# BikerBlinker.net
KiCad netlist of a schematic drawn in Altium Designer
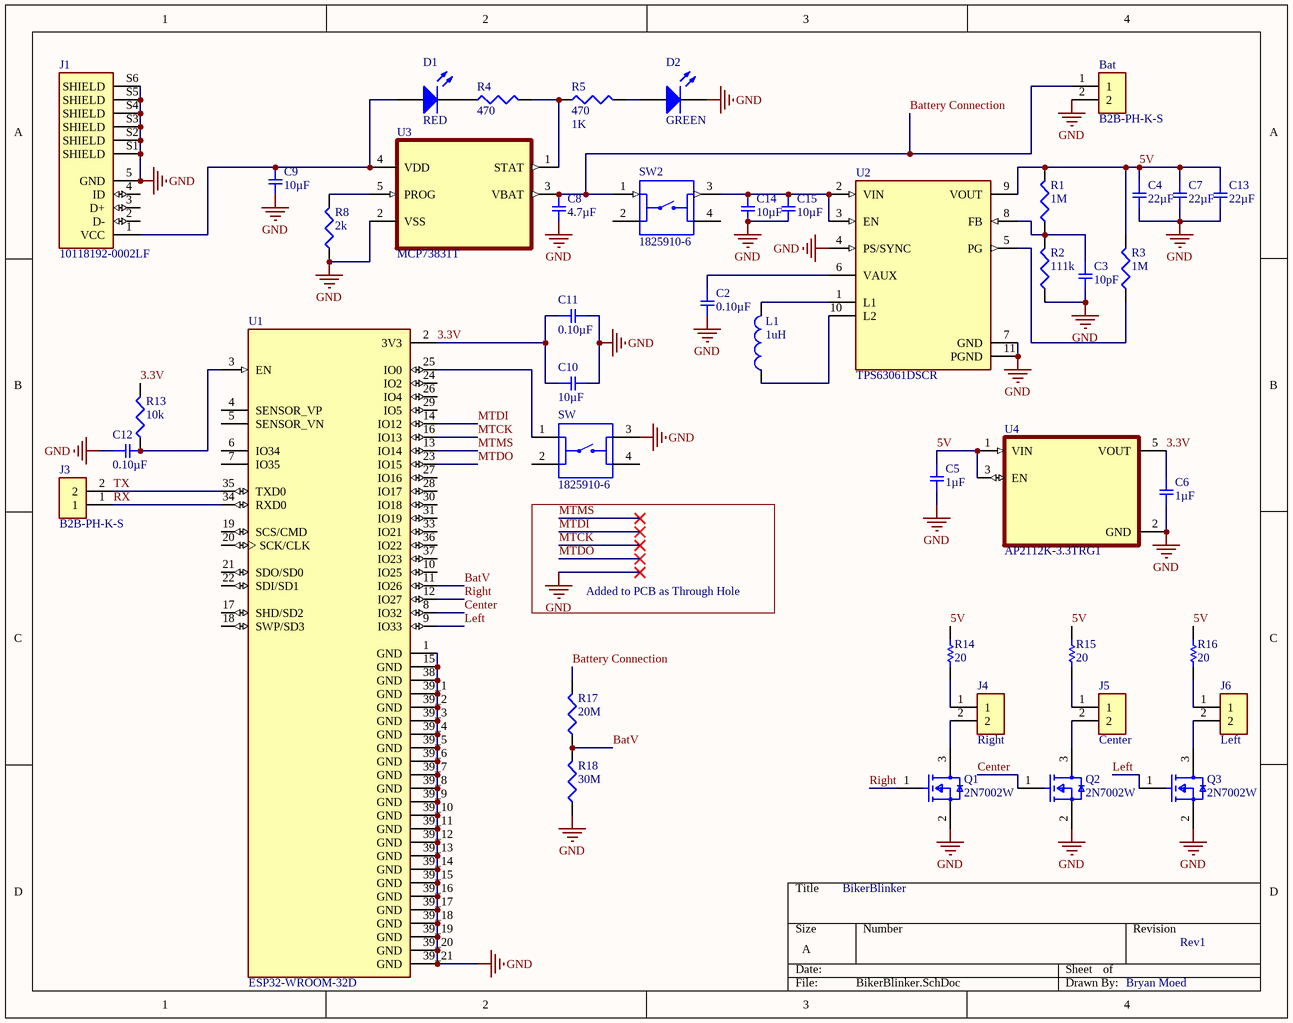
[diagram p0: BikerBlinker.SchDoc]

(export (version "E")
  (design (tool "Eeschema 10.0.6"))
  (components
    (comp (ref "Bat")
      (value "B2B-PH-K-S")
      (footprint "JST_B2B-PH-K-S(LF)(SN)")
      (description "Connector Header Through Hole 2 position 0.079 _2.00mm_")
      (fields (field (name "MF") "JST Sales") (field (name "MP") "B2B-PH-K-S_LF__SN_"))
      (libsource (lib "") (part "B2B-PH-K-S(LF)(SN)_1"))
    )
    (comp (ref "C2")
      (value "0.10µF")
      (footprint "SMD-0603C")
      (description "CAP CER 0.1UF 16V X7R 0603")
      (fields
        (field (name "DIGI-KEY PART NUMBER") "490-5796-1-ND")
        (field (name "PART NUMBER") "GCJ188R71C104KA01D")
      )
      (libsource (lib "capacitor_murata_0603") (part "GCJ188R71C104KA01D"))
    )
    (comp (ref "C3")
      (value "10pF")
      (footprint "SMD-0603C")
      (description "CAP CER 10PF 50V NP0 0603")
      (fields
        (field (name "DIGI-KEY PART NUMBER") "490-12530-1-ND")
        (field (name "PART NUMBER") "GCM1885C1H100FA16D")
      )
      (libsource (lib "capacitor_murata_0603") (part "GCM1885C1H100FA16D"))
    )
    (comp (ref "C4")
      (value "22µF")
      (footprint "SMD-0603C")
      (description "CAP CER 22UF 6.3V X5R 0603")
      (fields
        (field (name "DIGI-KEY PART NUMBER") "490-13241-1-ND")
        (field (name "PART NUMBER") "GRM186R60J226ME15D")
      )
      (libsource (lib "capacitor_murata_0603") (part "GRM186R60J226ME15D"))
    )
    (comp (ref "C5")
      (value "1µF")
      (footprint "SMD-0603C")
      (description "CAP CER 1UF 16V X7R 0603")
      (fields
        (field (name "DIGI-KEY PART NUMBER") "490-5241-1-ND")
        (field (name "PART NUMBER") "GCM188R71C105KA64D")
      )
      (libsource (lib "capacitor_murata_0603") (part "GCM188R71C105KA64D"))
    )
    (comp (ref "C6")
      (value "1µF")
      (footprint "SMD-0603C")
      (description "CAP CER 1UF 16V X7R 0603")
      (fields
        (field (name "DIGI-KEY PART NUMBER") "490-5241-1-ND")
        (field (name "PART NUMBER") "GCM188R71C105KA64D")
      )
      (libsource (lib "capacitor_murata_0603") (part "GCM188R71C105KA64D"))
    )
    (comp (ref "C7")
      (value "22µF")
      (footprint "SMD-0603C")
      (description "CAP CER 22UF 6.3V X5R 0603")
      (fields
        (field (name "DIGI-KEY PART NUMBER") "490-13241-1-ND")
        (field (name "PART NUMBER") "GRM186R60J226ME15D")
      )
      (libsource (lib "capacitor_murata_0603") (part "GRM186R60J226ME15D"))
    )
    (comp (ref "C8")
      (value "4.7µF")
      (footprint "SMD-0603C")
      (description "CAP CER 4.7UF 6.3V X7S 0603")
      (fields
        (field (name "DIGI-KEY PART NUMBER") "490-10884-1-ND")
        (field (name "PART NUMBER") "GRJ188C70J475KE11D")
      )
      (libsource (lib "capacitor_murata_0603") (part "GRJ188C70J475KE11D"))
    )
    (comp (ref "C9")
      (value "10µF")
      (footprint "SMD-0603C")
      (description "CAP CER 10UF 6.3V X5R 0603")
      (fields
        (field (name "DIGI-KEY PART NUMBER") "490-10467-1-ND")
        (field (name "PART NUMBER") "GRM185R60J106ME15D")
      )
      (libsource (lib "capacitor_murata_0603") (part "GRM185R60J106ME15D"))
    )
    (comp (ref "C10")
      (value "10µF")
      (footprint "SMD-0603C")
      (description "CAP CER 10UF 6.3V X5R 0603")
      (fields
        (field (name "DIGI-KEY PART NUMBER") "490-10467-1-ND")
        (field (name "PART NUMBER") "GRM185R60J106ME15D")
      )
      (libsource (lib "capacitor_murata_0603") (part "GRM185R60J106ME15D"))
    )
    (comp (ref "C11")
      (value "0.10µF")
      (footprint "SMD-0603C")
      (description "CAP CER 0.1UF 16V X7R 0603")
      (fields
        (field (name "DIGI-KEY PART NUMBER") "490-5796-1-ND")
        (field (name "PART NUMBER") "GCJ188R71C104KA01D")
      )
      (libsource (lib "capacitor_murata_0603") (part "GCJ188R71C104KA01D"))
    )
    (comp (ref "C12")
      (value "0.10µF")
      (footprint "SMD-0603C")
      (description "CAP CER 0.1UF 16V X7R 0603")
      (fields
        (field (name "DIGI-KEY PART NUMBER") "490-5796-1-ND")
        (field (name "PART NUMBER") "GCJ188R71C104KA01D")
      )
      (libsource (lib "capacitor_murata_0603") (part "GCJ188R71C104KA01D"))
    )
    (comp (ref "C13")
      (value "22µF")
      (footprint "SMD-0603C")
      (description "CAP CER 22UF 6.3V X5R 0603")
      (fields
        (field (name "DIGI-KEY PART NUMBER") "490-13241-1-ND")
        (field (name "PART NUMBER") "GRM186R60J226ME15D")
      )
      (libsource (lib "capacitor_murata_0603") (part "GRM186R60J226ME15D"))
    )
    (comp (ref "C14")
      (value "10µF")
      (footprint "SMD-0603C")
      (description "CAP CER 10UF 6.3V X5R 0603")
      (fields
        (field (name "DIGI-KEY PART NUMBER") "490-10467-1-ND")
        (field (name "PART NUMBER") "GRM185R60J106ME15D")
      )
      (libsource (lib "capacitor_murata_0603") (part "GRM185R60J106ME15D"))
    )
    (comp (ref "C15")
      (value "10µF")
      (footprint "SMD-0603C")
      (description "CAP CER 10UF 6.3V X5R 0603")
      (fields
        (field (name "DIGI-KEY PART NUMBER") "490-10467-1-ND")
        (field (name "PART NUMBER") "GRM185R60J106ME15D")
      )
      (libsource (lib "capacitor_murata_0603") (part "GRM185R60J106ME15D"))
    )
    (comp (ref "D1")
      (value "RED")
      (footprint "J1-0603")
      (description "Typical RED GaAs LED")
      (fields (field (name "PUBLISHER") "Altium Limited"))
      (libsource (lib "Miscellaneous Devices") (part "LED1"))
    )
    (comp (ref "D2")
      (value "GREEN")
      (footprint "J1-0603")
      (description "Typical RED GaAs LED")
      (fields (field (name "PUBLISHER") "Altium Limited"))
      (libsource (lib "Miscellaneous Devices") (part "LED1"))
    )
    (comp (ref "J1")
      (value "10118192-0002LF")
      (footprint "AMPHENOL_10118192-0002LF")
      (description "USB - micro B USB 2.0 Receptacle Connector 5 Position Surface Mount, Right Angle")
      (fields (field (name "MF") "Amphenol ICC"))
      (libsource (lib "10118192-0002LF") (part "10118192-0002LF"))
    )
    (comp (ref "J3")
      (value "B2B-PH-K-S")
      (footprint "JST_B2B-PH-K-S(LF)(SN)")
      (description "Connector Header Through Hole 2 position 0.079 _2.00mm_")
      (fields (field (name "MF") "JST Sales") (field (name "MP") "B2B-PH-K-S_LF__SN_"))
      (libsource (lib "B2B-PH-K-S_LF__SN_") (part "B2B-PH-K-S(LF)(SN)"))
    )
    (comp (ref "J4")
      (value "Right")
      (footprint "JST_B2B-PH-K-S(LF)(SN)")
      (description "Connector Header Through Hole 2 position 0.079 _2.00mm_")
      (fields (field (name "MF") "JST Sales") (field (name "MP") "B2B-PH-K-S_LF__SN_"))
      (libsource (lib "") (part "B2B-PH-K-S(LF)(SN)_1"))
    )
    (comp (ref "J5")
      (value "Center")
      (footprint "JST_B2B-PH-K-S(LF)(SN)")
      (description "Connector Header Through Hole 2 position 0.079 _2.00mm_")
      (fields (field (name "MF") "JST Sales") (field (name "MP") "B2B-PH-K-S_LF__SN_"))
      (libsource (lib "") (part "B2B-PH-K-S(LF)(SN)_1"))
    )
    (comp (ref "J6")
      (value "Left")
      (footprint "JST_B2B-PH-K-S(LF)(SN)")
      (description "Connector Header Through Hole 2 position 0.079 _2.00mm_")
      (fields (field (name "MF") "JST Sales") (field (name "MP") "B2B-PH-K-S_LF__SN_"))
      (libsource (lib "") (part "B2B-PH-K-S(LF)(SN)_1"))
    )
    (comp (ref "L1")
      (value "1uH")
      (footprint "0603")
      (description "Inductor")
      (fields (field (name "PUBLISHER") "Altium Limited"))
      (libsource (lib "Miscellaneous Devices") (part "Inductor"))
    )
    (comp (ref "Q1")
      (value "2N7002W")
      (footprint "FP-419AB-01-IPC_C")
      (description "MOSFET N-CH 60V 115MA SOT-323")
      (libsource (lib "Altium Content Vault") (part "a04dfd38ebfed9f67ad7f4c51a87371"))
    )
    (comp (ref "Q2")
      (value "2N7002W")
      (footprint "FP-419AB-01-IPC_C")
      (description "MOSFET N-CH 60V 115MA SOT-323")
      (libsource (lib "Altium Content Vault") (part "a04dfd38ebfed9f67ad7f4c51a87371"))
    )
    (comp (ref "Q3")
      (value "2N7002W")
      (footprint "FP-419AB-01-IPC_C")
      (description "MOSFET N-CH 60V 115MA SOT-323")
      (libsource (lib "Altium Content Vault") (part "a04dfd38ebfed9f67ad7f4c51a87371"))
    )
    (comp (ref "R1")
      (value "1M")
      (footprint "J1-0603")
      (description "Resistor")
      (fields (field (name "PUBLISHER") "Altium Limited"))
      (libsource (lib "Miscellaneous Devices") (part "Res3"))
    )
    (comp (ref "R2")
      (value "111k")
      (footprint "J1-0603")
      (description "Resistor")
      (fields (field (name "PUBLISHER") "Altium Limited"))
      (libsource (lib "Miscellaneous Devices") (part "Res3"))
    )
    (comp (ref "R3")
      (value "1M")
      (footprint "J1-0603")
      (description "Resistor")
      (fields (field (name "PUBLISHER") "Altium Limited"))
      (libsource (lib "Miscellaneous Devices") (part "Res3"))
    )
    (comp (ref "R4")
      (value "470")
      (footprint "J1-0603")
      (description "Resistor")
      (fields (field (name "PUBLISHER") "Altium Limited"))
      (libsource (lib "Miscellaneous Devices") (part "Res3"))
    )
    (comp (ref "R5")
      (value "470")
      (footprint "J1-0603")
      (description "Resistor")
      (fields (field (name "ALTIUM_VALUE") "1K") (field (name "PUBLISHER") "Altium Limited"))
      (libsource (lib "Miscellaneous Devices") (part "Res3"))
    )
    (comp (ref "R8")
      (value "2k")
      (footprint "J1-0603")
      (description "Resistor")
      (fields (field (name "PUBLISHER") "Altium Limited"))
      (libsource (lib "Miscellaneous Devices") (part "Res3"))
    )
    (comp (ref "R13")
      (value "10k")
      (footprint "J1-0603")
      (description "Resistor")
      (fields (field (name "PUBLISHER") "Altium Limited"))
      (libsource (lib "Miscellaneous Devices") (part "Res3"))
    )
    (comp (ref "R14")
      (value "20")
      (footprint "AXIAL-0.3")
      (description "Resistor")
      (fields (field (name "PUBLISHER") "Altium Limited"))
      (libsource (lib "Miscellaneous Devices") (part "Res1"))
    )
    (comp (ref "R15")
      (value "20")
      (footprint "AXIAL-0.3")
      (description "Resistor")
      (fields (field (name "PUBLISHER") "Altium Limited"))
      (libsource (lib "Miscellaneous Devices") (part "Res1"))
    )
    (comp (ref "R16")
      (value "20")
      (footprint "AXIAL-0.3")
      (description "Resistor")
      (fields (field (name "PUBLISHER") "Altium Limited"))
      (libsource (lib "Miscellaneous Devices") (part "Res1"))
    )
    (comp (ref "R17")
      (value "20M")
      (footprint "J1-0603")
      (description "Resistor")
      (fields (field (name "PUBLISHER") "Altium Limited"))
      (libsource (lib "Miscellaneous Devices") (part "Res3"))
    )
    (comp (ref "R18")
      (value "30M")
      (footprint "J1-0603")
      (description "Resistor")
      (fields (field (name "PUBLISHER") "Altium Limited"))
      (libsource (lib "Miscellaneous Devices") (part "Res3"))
    )
    (comp (ref "SW")
      (value "1825910-6")
      (footprint "SW_1825910-6-4")
      (description "Switch Push Button OFF _ON_ SPST Round Button 0.05A 24VDC Momentary Contact PC Pins Thru-Hole")
      (fields (field (name "MF") "TE Connectivity") (field (name "DIGI-KEY_PART_NUMBER") "450-1650-ND"))
      (libsource (lib "1825910-6") (part "1825910-6"))
    )
    (comp (ref "SW2")
      (value "1825910-6")
      (footprint "SW_1825910-6-4")
      (description "Switch Push Button OFF _ON_ SPST Round Button 0.05A 24VDC Momentary Contact PC Pins Thru-Hole")
      (fields (field (name "MF") "TE Connectivity") (field (name "DIGI-KEY_PART_NUMBER") "450-1650-ND"))
      (libsource (lib "1825910-6") (part "1825910-6"))
    )
    (comp (ref "U1")
      (value "ESP32-WROOM-32D")
      (footprint "MODULE_ESP32-WROOM-32D")
      (fields (field (name "MF") "Espressif Systems"))
      (libsource (lib "ESP32-WROOM-32D") (part "ESP32-WROOM-32D"))
    )
    (comp (ref "U2")
      (value "TPS63061DSCR")
      (footprint "CONV_TPS63061DSCR")
      (libsource (lib "TPS63061DSCR") (part "TPS63061DSCR"))
    )
    (comp (ref "U3")
      (value "MCP73831T")
      (footprint "SOT95P280X145-5N")
      (description "Charger IC Lithium Ion/Polymer SOT-23-5")
      (fields (field (name "MP") "MCP73831T-4ADI/OT") (field (name "MF") "Microchip"))
      (libsource (lib "MCP73831T-4ADI_OT") (part "MCP73831T-4ADI/OT"))
    )
    (comp (ref "U4")
      (value "AP2112K-3.3TRG1")
      (footprint "SOT95P285X140-5N")
      (description "Linear Voltage Regulator IC 1 Output 600mA SOT-25")
      (fields (field (name "MF") "Diodes Inc."))
      (libsource (lib "AP2112K-1.8TRG1") (part "AP2112K-1.8TRG1"))
    )
  )
  (nets
    (net (code "1") (name "/3.3V") (class "Default")
      (node (ref "C10") (pin "1") (pinfunction "1_1") (pintype "passive"))
      (node (ref "C11") (pin "1") (pinfunction "1_1") (pintype "passive"))
      (node (ref "C6") (pin "1") (pinfunction "1_1") (pintype "passive"))
      (node (ref "R13") (pin "2") (pinfunction "2_2") (pintype "passive"))
      (node (ref "U1") (pin "2") (pinfunction "3V3_2") (pintype "power_in"))
      (node (ref "U4") (pin "5") (pinfunction "VOUT_5") (pintype "power_in"))
    )
    (net (code "2") (name "/5V") (class "Default")
      (node (ref "C13") (pin "1") (pinfunction "1_1") (pintype "passive"))
      (node (ref "C4") (pin "1") (pinfunction "1_1") (pintype "passive"))
      (node (ref "C5") (pin "1") (pinfunction "1_1") (pintype "passive"))
      (node (ref "C7") (pin "1") (pinfunction "1_1") (pintype "passive"))
      (node (ref "R1") (pin "2") (pinfunction "2_2") (pintype "passive"))
      (node (ref "R14") (pin "2") (pinfunction "2_2") (pintype "passive"))
      (node (ref "R15") (pin "2") (pinfunction "2_2") (pintype "passive"))
      (node (ref "R16") (pin "2") (pinfunction "2_2") (pintype "passive"))
      (node (ref "R3") (pin "2") (pinfunction "2_2") (pintype "passive"))
      (node (ref "U2") (pin "9") (pinfunction "VOUT_9") (pintype "power_in"))
      (node (ref "U4") (pin "1") (pinfunction "VIN_1") (pintype "input"))
      (node (ref "U4") (pin "3") (pinfunction "EN_3") (pintype "bidirectional"))
    )
    (net (code "3") (name "/BatV") (class "Default")
      (node (ref "R17") (pin "1") (pinfunction "1_1") (pintype "passive"))
      (node (ref "R18") (pin "2") (pinfunction "2_2") (pintype "passive"))
      (node (ref "U1") (pin "11") (pinfunction "IO26_11") (pintype "bidirectional"))
    )
    (net (code "4") (name "/Battery Connection") (class "Default")
      (node (ref "Bat") (pin "1") (pinfunction "1_1") (pintype "passive"))
      (node (ref "C8") (pin "1") (pinfunction "1_1") (pintype "passive"))
      (node (ref "R17") (pin "2") (pinfunction "2_2") (pintype "passive"))
      (node (ref "SW2") (pin "1") (pinfunction "1_1") (pintype "passive"))
      (node (ref "U3") (pin "3") (pinfunction "VBAT_3") (pintype "output"))
    )
    (net (code "5") (name "/Center") (class "Default")
      (node (ref "Q2") (pin "1") (pinfunction "Gate_1") (pintype "passive"))
      (node (ref "U1") (pin "8") (pinfunction "IO32_8") (pintype "bidirectional"))
    )
    (net (code "6") (name "/Left") (class "Default")
      (node (ref "Q3") (pin "1") (pinfunction "Gate_1") (pintype "passive"))
      (node (ref "U1") (pin "9") (pinfunction "IO33_9") (pintype "bidirectional"))
    )
    (net (code "7") (name "/MTCK") (class "Default")
      (node (ref "U1") (pin "16") (pinfunction "IO13_16") (pintype "bidirectional"))
    )
    (net (code "8") (name "/MTDI") (class "Default")
      (node (ref "U1") (pin "14") (pinfunction "IO12_14") (pintype "bidirectional"))
    )
    (net (code "9") (name "/MTDO") (class "Default")
      (node (ref "U1") (pin "23") (pinfunction "IO15_23") (pintype "bidirectional"))
    )
    (net (code "10") (name "/MTMS") (class "Default")
      (node (ref "U1") (pin "13") (pinfunction "IO14_13") (pintype "bidirectional"))
    )
    (net (code "11") (name "/RX") (class "Default")
      (node (ref "J3") (pin "1") (pinfunction "1_1") (pintype "passive"))
      (node (ref "U1") (pin "34") (pinfunction "RXD0_34") (pintype "bidirectional"))
    )
    (net (code "12") (name "/Right") (class "Default")
      (node (ref "Q1") (pin "1") (pinfunction "Gate_1") (pintype "passive"))
      (node (ref "U1") (pin "12") (pinfunction "IO27_12") (pintype "bidirectional"))
    )
    (net (code "13") (name "/TX") (class "Default")
      (node (ref "J3") (pin "2") (pinfunction "2_2") (pintype "passive"))
      (node (ref "U1") (pin "35") (pinfunction "TXD0_35") (pintype "bidirectional"))
    )
    (net (code "14") (name "GND") (class "Default")
      (node (ref "Bat") (pin "2") (pinfunction "2_2") (pintype "passive"))
      (node (ref "C10") (pin "2") (pinfunction "2_2") (pintype "passive"))
      (node (ref "C11") (pin "2") (pinfunction "2_2") (pintype "passive"))
      (node (ref "C12") (pin "1") (pinfunction "1_1") (pintype "passive"))
      (node (ref "C13") (pin "2") (pinfunction "2_2") (pintype "passive"))
      (node (ref "C14") (pin "2") (pinfunction "2_2") (pintype "passive"))
      (node (ref "C15") (pin "2") (pinfunction "2_2") (pintype "passive"))
      (node (ref "C2") (pin "2") (pinfunction "2_2") (pintype "passive"))
      (node (ref "C3") (pin "2") (pinfunction "2_2") (pintype "passive"))
      (node (ref "C4") (pin "2") (pinfunction "2_2") (pintype "passive"))
      (node (ref "C5") (pin "2") (pinfunction "2_2") (pintype "passive"))
      (node (ref "C6") (pin "2") (pinfunction "2_2") (pintype "passive"))
      (node (ref "C7") (pin "2") (pinfunction "2_2") (pintype "passive"))
      (node (ref "C8") (pin "2") (pinfunction "2_2") (pintype "passive"))
      (node (ref "C9") (pin "2") (pinfunction "2_2") (pintype "passive"))
      (node (ref "D2") (pin "2") (pinfunction "K_2") (pintype "passive"))
      (node (ref "J1") (pin "5") (pinfunction "GND_5") (pintype "power_in"))
      (node (ref "J1") (pin "S1") (pinfunction "SHIELD_S1") (pintype "passive"))
      (node (ref "J1") (pin "S2") (pinfunction "SHIELD_S2") (pintype "passive"))
      (node (ref "J1") (pin "S3") (pinfunction "SHIELD_S3") (pintype "passive"))
      (node (ref "J1") (pin "S4") (pinfunction "SHIELD_S4") (pintype "passive"))
      (node (ref "J1") (pin "S5") (pinfunction "SHIELD_S5") (pintype "passive"))
      (node (ref "J1") (pin "S6") (pinfunction "SHIELD_S6") (pintype "passive"))
      (node (ref "Q1") (pin "2") (pinfunction "Source_2") (pintype "passive"))
      (node (ref "Q2") (pin "2") (pinfunction "Source_2") (pintype "passive"))
      (node (ref "Q3") (pin "2") (pinfunction "Source_2") (pintype "passive"))
      (node (ref "R18") (pin "1") (pinfunction "1_1") (pintype "passive"))
      (node (ref "R2") (pin "1") (pinfunction "1_1") (pintype "passive"))
      (node (ref "R8") (pin "1") (pinfunction "1_1") (pintype "passive"))
      (node (ref "SW") (pin "3") (pinfunction "3_3") (pintype "passive"))
      (node (ref "U1") (pin "1") (pinfunction "GND_1") (pintype "power_in"))
      (node (ref "U1") (pin "15") (pinfunction "GND_15") (pintype "power_in"))
      (node (ref "U1") (pin "38") (pinfunction "GND_38") (pintype "power_in"))
      (node (ref "U1") (pin "39_1") (pinfunction "GND_39_1") (pintype "power_in"))
      (node (ref "U1") (pin "39_10") (pinfunction "GND_39_10") (pintype "power_in"))
      (node (ref "U1") (pin "39_11") (pinfunction "GND_39_11") (pintype "power_in"))
      (node (ref "U1") (pin "39_12") (pinfunction "GND_39_12") (pintype "power_in"))
      (node (ref "U1") (pin "39_13") (pinfunction "GND_39_13") (pintype "power_in"))
      (node (ref "U1") (pin "39_14") (pinfunction "GND_39_14") (pintype "power_in"))
      (node (ref "U1") (pin "39_15") (pinfunction "GND_39_15") (pintype "power_in"))
      (node (ref "U1") (pin "39_16") (pinfunction "GND_39_16") (pintype "power_in"))
      (node (ref "U1") (pin "39_17") (pinfunction "GND_39_17") (pintype "power_in"))
      (node (ref "U1") (pin "39_18") (pinfunction "GND_39_18") (pintype "power_in"))
      (node (ref "U1") (pin "39_19") (pinfunction "GND_39_19") (pintype "power_in"))
      (node (ref "U1") (pin "39_2") (pinfunction "GND_39_2") (pintype "power_in"))
      (node (ref "U1") (pin "39_20") (pinfunction "GND_39_20") (pintype "power_in"))
      (node (ref "U1") (pin "39_21") (pinfunction "GND_39_21") (pintype "power_in"))
      (node (ref "U1") (pin "39_3") (pinfunction "GND_39_3") (pintype "power_in"))
      (node (ref "U1") (pin "39_4") (pinfunction "GND_39_4") (pintype "power_in"))
      (node (ref "U1") (pin "39_5") (pinfunction "GND_39_5") (pintype "power_in"))
      (node (ref "U1") (pin "39_6") (pinfunction "GND_39_6") (pintype "power_in"))
      (node (ref "U1") (pin "39_7") (pinfunction "GND_39_7") (pintype "power_in"))
      (node (ref "U1") (pin "39_8") (pinfunction "GND_39_8") (pintype "power_in"))
      (node (ref "U1") (pin "39_9") (pinfunction "GND_39_9") (pintype "power_in"))
      (node (ref "U2") (pin "11") (pinfunction "PGND_11") (pintype "power_in"))
      (node (ref "U2") (pin "4") (pinfunction "PS/SYNC_4") (pintype "input"))
      (node (ref "U2") (pin "7") (pinfunction "GND_7") (pintype "power_in"))
      (node (ref "U3") (pin "2") (pinfunction "VSS_2") (pintype "power_in"))
      (node (ref "U4") (pin "2") (pinfunction "GND_2") (pintype "power_in"))
    )
    (net (code "15") (name "Net-(D1-A)") (class "Default")
      (node (ref "C9") (pin "1") (pinfunction "1_1") (pintype "passive"))
      (node (ref "D1") (pin "1") (pinfunction "A_1") (pintype "passive"))
      (node (ref "J1") (pin "1") (pinfunction "VCC_1") (pintype "power_in"))
      (node (ref "U3") (pin "4") (pinfunction "VDD_4") (pintype "power_in"))
    )
    (net (code "16") (name "Net-(D1-K)") (class "Default")
      (node (ref "D1") (pin "2") (pinfunction "K_2") (pintype "passive"))
      (node (ref "R4") (pin "1") (pinfunction "1_1") (pintype "passive"))
    )
    (net (code "17") (name "Net-(D2-A)") (class "Default")
      (node (ref "D2") (pin "1") (pinfunction "A_1") (pintype "passive"))
      (node (ref "R5") (pin "2") (pinfunction "2_2") (pintype "passive"))
    )
    (net (code "18") (name "Net-(J4-Pad1)") (class "Default")
      (node (ref "J4") (pin "1") (pinfunction "1_1") (pintype "passive"))
      (node (ref "R14") (pin "1") (pinfunction "1_1") (pintype "passive"))
    )
    (net (code "19") (name "Net-(J5-Pad1)") (class "Default")
      (node (ref "J5") (pin "1") (pinfunction "1_1") (pintype "passive"))
      (node (ref "R15") (pin "1") (pinfunction "1_1") (pintype "passive"))
    )
    (net (code "20") (name "Net-(J6-Pad1)") (class "Default")
      (node (ref "J6") (pin "1") (pinfunction "1_1") (pintype "passive"))
      (node (ref "R16") (pin "1") (pinfunction "1_1") (pintype "passive"))
    )
    (net (code "21") (name "Net-(Q1-Drain)") (class "Default")
      (node (ref "J4") (pin "2") (pinfunction "2_2") (pintype "passive"))
      (node (ref "Q1") (pin "3") (pinfunction "Drain_3") (pintype "passive"))
    )
    (net (code "22") (name "Net-(Q2-Drain)") (class "Default")
      (node (ref "J5") (pin "2") (pinfunction "2_2") (pintype "passive"))
      (node (ref "Q2") (pin "3") (pinfunction "Drain_3") (pintype "passive"))
    )
    (net (code "23") (name "Net-(Q3-Drain)") (class "Default")
      (node (ref "J6") (pin "2") (pinfunction "2_2") (pintype "passive"))
      (node (ref "Q3") (pin "3") (pinfunction "Drain_3") (pintype "passive"))
    )
    (net (code "24") (name "Net-(U1-EN)") (class "Default")
      (node (ref "C12") (pin "2") (pinfunction "2_2") (pintype "passive"))
      (node (ref "R13") (pin "1") (pinfunction "1_1") (pintype "passive"))
      (node (ref "U1") (pin "3") (pinfunction "EN_3") (pintype "input"))
    )
    (net (code "25") (name "Net-(U1-IO0)") (class "Default")
      (node (ref "SW") (pin "1") (pinfunction "1_1") (pintype "passive"))
      (node (ref "U1") (pin "25") (pinfunction "IO0_25") (pintype "bidirectional"))
    )
    (net (code "26") (name "Net-(U2-EN)") (class "Default")
      (node (ref "C14") (pin "1") (pinfunction "1_1") (pintype "passive"))
      (node (ref "C15") (pin "1") (pinfunction "1_1") (pintype "passive"))
      (node (ref "SW2") (pin "3") (pinfunction "3_3") (pintype "passive"))
      (node (ref "U2") (pin "2") (pinfunction "VIN_2") (pintype "input"))
      (node (ref "U2") (pin "3") (pinfunction "EN_3") (pintype "input"))
    )
    (net (code "27") (name "Net-(U2-FB)") (class "Default")
      (node (ref "C3") (pin "1") (pinfunction "1_1") (pintype "passive"))
      (node (ref "R1") (pin "1") (pinfunction "1_1") (pintype "passive"))
      (node (ref "R2") (pin "2") (pinfunction "2_2") (pintype "passive"))
      (node (ref "U2") (pin "8") (pinfunction "FB_8") (pintype "input"))
    )
    (net (code "28") (name "Net-(U2-L1)") (class "Default")
      (node (ref "L1") (pin "2") (pinfunction "2_2") (pintype "passive"))
      (node (ref "U2") (pin "1") (pinfunction "L1_1") (pintype "passive"))
    )
    (net (code "29") (name "Net-(U2-L2)") (class "Default")
      (node (ref "L1") (pin "1") (pinfunction "1_1") (pintype "passive"))
      (node (ref "U2") (pin "10") (pinfunction "L2_10") (pintype "passive"))
    )
    (net (code "30") (name "Net-(U2-PG)") (class "Default")
      (node (ref "R3") (pin "1") (pinfunction "1_1") (pintype "passive"))
      (node (ref "U2") (pin "5") (pinfunction "PG_5") (pintype "output"))
    )
    (net (code "31") (name "Net-(U2-VAUX)") (class "Default")
      (node (ref "C2") (pin "1") (pinfunction "1_1") (pintype "passive"))
      (node (ref "U2") (pin "6") (pinfunction "VAUX_6") (pintype "passive"))
    )
    (net (code "32") (name "Net-(U3-PROG)") (class "Default")
      (node (ref "R8") (pin "2") (pinfunction "2_2") (pintype "passive"))
      (node (ref "U3") (pin "5") (pinfunction "PROG_5") (pintype "input"))
    )
    (net (code "33") (name "Net-(U3-STAT)") (class "Default")
      (node (ref "R4") (pin "2") (pinfunction "2_2") (pintype "passive"))
      (node (ref "R5") (pin "1") (pinfunction "1_1") (pintype "passive"))
      (node (ref "U3") (pin "1") (pinfunction "STAT_1") (pintype "output"))
    )
    (net (code "34") (name "unconnected-(J1-D+-Pad3)") (class "Default")
      (node (ref "J1") (pin "3") (pinfunction "D+_3") (pintype "bidirectional"))
    )
    (net (code "35") (name "unconnected-(J1-D--Pad2)") (class "Default")
      (node (ref "J1") (pin "2") (pinfunction "D-_2") (pintype "bidirectional"))
    )
    (net (code "36") (name "unconnected-(J1-ID-Pad4)") (class "Default")
      (node (ref "J1") (pin "4") (pinfunction "ID_4") (pintype "bidirectional"))
    )
    (net (code "37") (name "unconnected-(SW-Pad2)") (class "Default")
      (node (ref "SW") (pin "2") (pinfunction "2_2") (pintype "passive"))
    )
    (net (code "38") (name "unconnected-(SW-Pad4)") (class "Default")
      (node (ref "SW") (pin "4") (pinfunction "4_4") (pintype "passive"))
    )
    (net (code "39") (name "unconnected-(SW2-Pad2)") (class "Default")
      (node (ref "SW2") (pin "2") (pinfunction "2_2") (pintype "passive"))
    )
    (net (code "40") (name "unconnected-(SW2-Pad4)") (class "Default")
      (node (ref "SW2") (pin "4") (pinfunction "4_4") (pintype "passive"))
    )
    (net (code "41") (name "unconnected-(U1-IO2-Pad24)") (class "Default")
      (node (ref "U1") (pin "24") (pinfunction "IO2_24") (pintype "bidirectional"))
    )
    (net (code "42") (name "unconnected-(U1-IO4-Pad26)") (class "Default")
      (node (ref "U1") (pin "26") (pinfunction "IO4_26") (pintype "bidirectional"))
    )
    (net (code "43") (name "unconnected-(U1-IO5-Pad29)") (class "Default")
      (node (ref "U1") (pin "29") (pinfunction "IO5_29") (pintype "bidirectional"))
    )
    (net (code "44") (name "unconnected-(U1-IO16-Pad27)") (class "Default")
      (node (ref "U1") (pin "27") (pinfunction "IO16_27") (pintype "bidirectional"))
    )
    (net (code "45") (name "unconnected-(U1-IO17-Pad28)") (class "Default")
      (node (ref "U1") (pin "28") (pinfunction "IO17_28") (pintype "bidirectional"))
    )
    (net (code "46") (name "unconnected-(U1-IO18-Pad30)") (class "Default")
      (node (ref "U1") (pin "30") (pinfunction "IO18_30") (pintype "bidirectional"))
    )
    (net (code "47") (name "unconnected-(U1-IO19-Pad31)") (class "Default")
      (node (ref "U1") (pin "31") (pinfunction "IO19_31") (pintype "bidirectional"))
    )
    (net (code "48") (name "unconnected-(U1-IO21-Pad33)") (class "Default")
      (node (ref "U1") (pin "33") (pinfunction "IO21_33") (pintype "bidirectional"))
    )
    (net (code "49") (name "unconnected-(U1-IO22-Pad36)") (class "Default")
      (node (ref "U1") (pin "36") (pinfunction "IO22_36") (pintype "bidirectional"))
    )
    (net (code "50") (name "unconnected-(U1-IO23-Pad37)") (class "Default")
      (node (ref "U1") (pin "37") (pinfunction "IO23_37") (pintype "bidirectional"))
    )
    (net (code "51") (name "unconnected-(U1-IO25-Pad10)") (class "Default")
      (node (ref "U1") (pin "10") (pinfunction "IO25_10") (pintype "bidirectional"))
    )
    (net (code "52") (name "unconnected-(U1-IO34-Pad6)") (class "Default")
      (node (ref "U1") (pin "6") (pinfunction "IO34_6") (pintype "passive"))
    )
    (net (code "53") (name "unconnected-(U1-IO35-Pad7)") (class "Default")
      (node (ref "U1") (pin "7") (pinfunction "IO35_7") (pintype "passive"))
    )
    (net (code "54") (name "unconnected-(U1-SCK{slash}CLK-Pad20)") (class "Default")
      (node (ref "U1") (pin "20") (pinfunction "SCK/CLK_20") (pintype "bidirectional"))
    )
    (net (code "55") (name "unconnected-(U1-SCS{slash}CMD-Pad19)") (class "Default")
      (node (ref "U1") (pin "19") (pinfunction "SCS/CMD_19") (pintype "bidirectional"))
    )
    (net (code "56") (name "unconnected-(U1-SDI{slash}SD1-Pad22)") (class "Default")
      (node (ref "U1") (pin "22") (pinfunction "SDI/SD1_22") (pintype "bidirectional"))
    )
    (net (code "57") (name "unconnected-(U1-SDO{slash}SD0-Pad21)") (class "Default")
      (node (ref "U1") (pin "21") (pinfunction "SDO/SD0_21") (pintype "bidirectional"))
    )
    (net (code "58") (name "unconnected-(U1-SENSOR_VN-Pad5)") (class "Default")
      (node (ref "U1") (pin "5") (pinfunction "SENSOR_VN_5") (pintype "passive"))
    )
    (net (code "59") (name "unconnected-(U1-SENSOR_VP-Pad4)") (class "Default")
      (node (ref "U1") (pin "4") (pinfunction "SENSOR_VP_4") (pintype "passive"))
    )
    (net (code "60") (name "unconnected-(U1-SHD{slash}SD2-Pad17)") (class "Default")
      (node (ref "U1") (pin "17") (pinfunction "SHD/SD2_17") (pintype "bidirectional"))
    )
    (net (code "61") (name "unconnected-(U1-SWP{slash}SD3-Pad18)") (class "Default")
      (node (ref "U1") (pin "18") (pinfunction "SWP/SD3_18") (pintype "bidirectional"))
    )
    (net (code "62") (name "unconnected-(U4-NC-Pad4)") (class "Default")
      (node (ref "U4") (pin "4") (pinfunction "NC_4") (pintype "bidirectional"))
    )
  )
)
